# Medida_corriente.net
KiCad netlist of a schematic drawn in Altium Designer
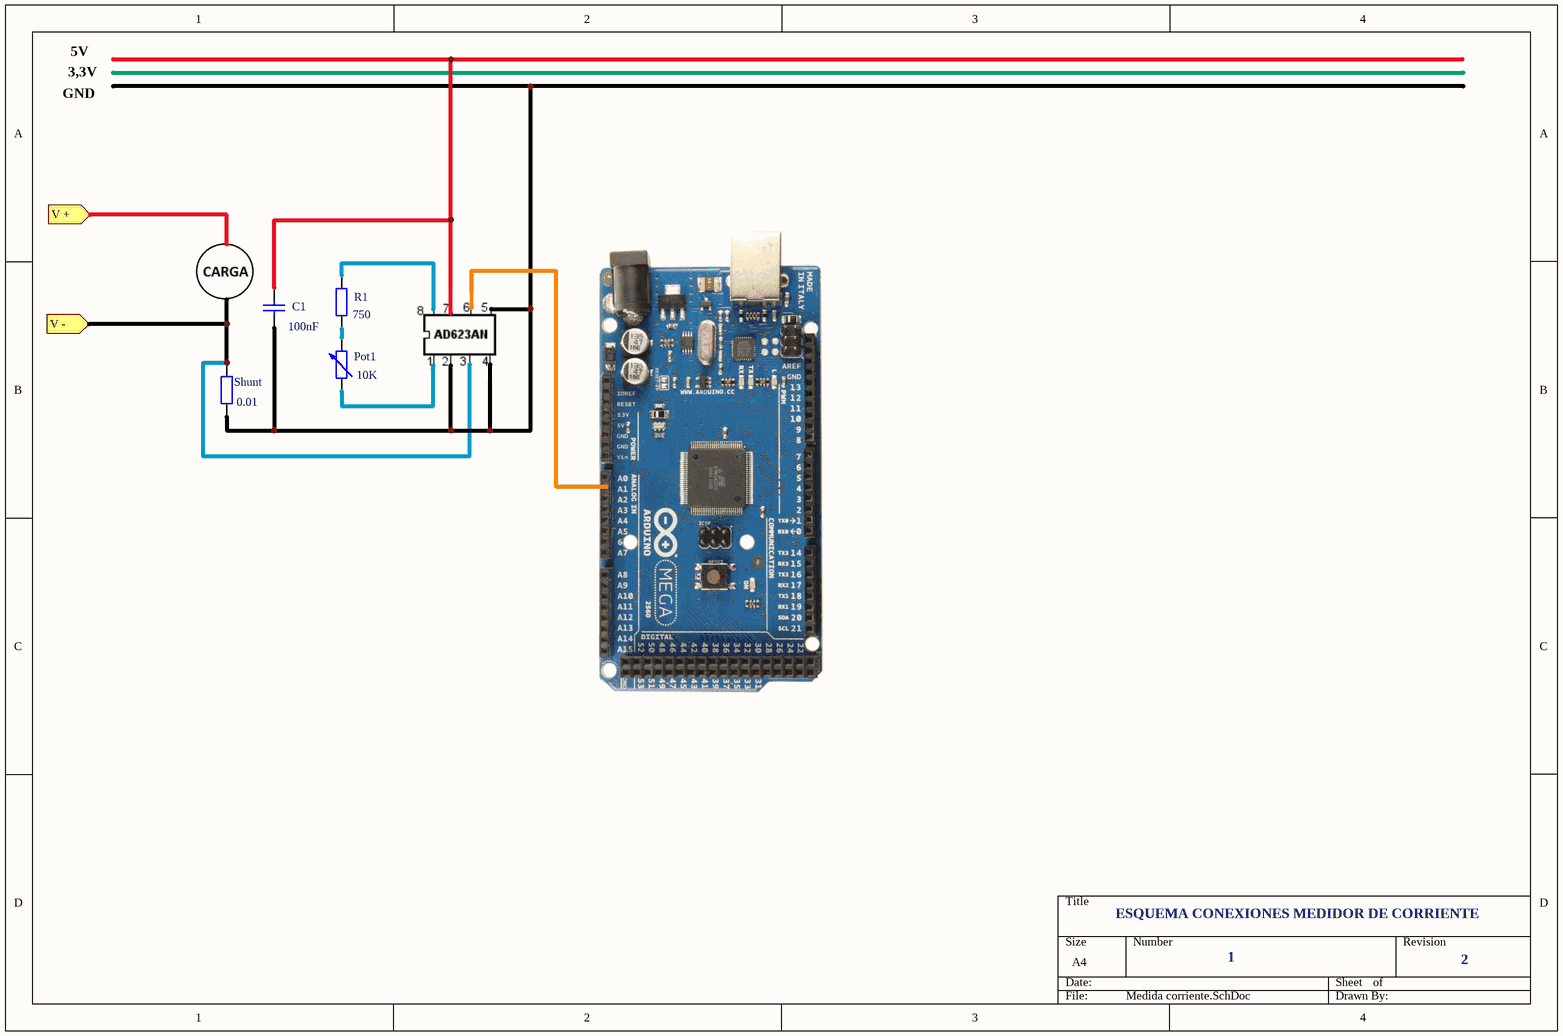
[diagram p0: Medida corriente.SchDoc]

(export (version "E")
  (design (tool "Eeschema 10.0.6"))
  (components
    (comp (ref "C1")
      (value "100nF")
      (footprint "RAD-0.3")
      (description "Capacitor")
      (fields (field (name "Comment") "Cap") (field (name "PUBLISHER") "Altium Limited"))
      (libsource (lib "Miscellaneous Devices") (part "Cap"))
    )
    (comp (ref "Pot1")
      (value "10K")
      (footprint "AXIAL-0.6")
      (description "Variable Resistor")
      (fields (field (name "Comment") "Res Adj2") (field (name "PUBLISHER") "Altium Limited"))
      (libsource (lib "Miscellaneous Devices") (part "Res Adj2"))
    )
    (comp (ref "R1")
      (value "750")
      (footprint "AXIAL-0.4")
      (description "Resistor")
      (fields (field (name "Comment") "Res2") (field (name "PUBLISHER") "Altium Limited"))
      (libsource (lib "Miscellaneous Devices") (part "Res2"))
    )
    (comp (ref "Shunt")
      (value "0.01")
      (footprint "AXIAL-0.4")
      (description "Resistor")
      (fields (field (name "Comment") "Res2") (field (name "PUBLISHER") "Altium Limited"))
      (libsource (lib "Miscellaneous Devices") (part "Res2"))
    )
  )
  (nets
    (net (code "2") (name "/V -") (class "Default")
      (node (ref "Shunt") (pin "2") (pinfunction "2_2") (pintype "passive"))
    )
    (net (code "3") (name "Net-(C1-Pad1)") (class "Default")
      (node (ref "C1") (pin "1") (pinfunction "1_1") (pintype "passive"))
      (node (ref "Shunt") (pin "1") (pinfunction "1_1") (pintype "passive"))
    )
    (net (code "4") (name "Net-(Pot1-Pad2)") (class "Default")
      (node (ref "Pot1") (pin "2") (pinfunction "2_2") (pintype "passive"))
      (node (ref "R1") (pin "1") (pinfunction "1_1") (pintype "passive"))
    )
    (net (code "5") (name "unconnected-(C1-Pad2)") (class "Default")
      (node (ref "C1") (pin "2") (pinfunction "2_2") (pintype "passive"))
    )
    (net (code "6") (name "unconnected-(Pot1-Pad1)") (class "Default")
      (node (ref "Pot1") (pin "1") (pinfunction "1_1") (pintype "passive"))
    )
    (net (code "7") (name "unconnected-(R1-Pad2)") (class "Default")
      (node (ref "R1") (pin "2") (pinfunction "2_2") (pintype "passive"))
    )
  )
)
